# custom_line_V1_comp.net
KiCad netlist of a schematic drawn in Altium Designer
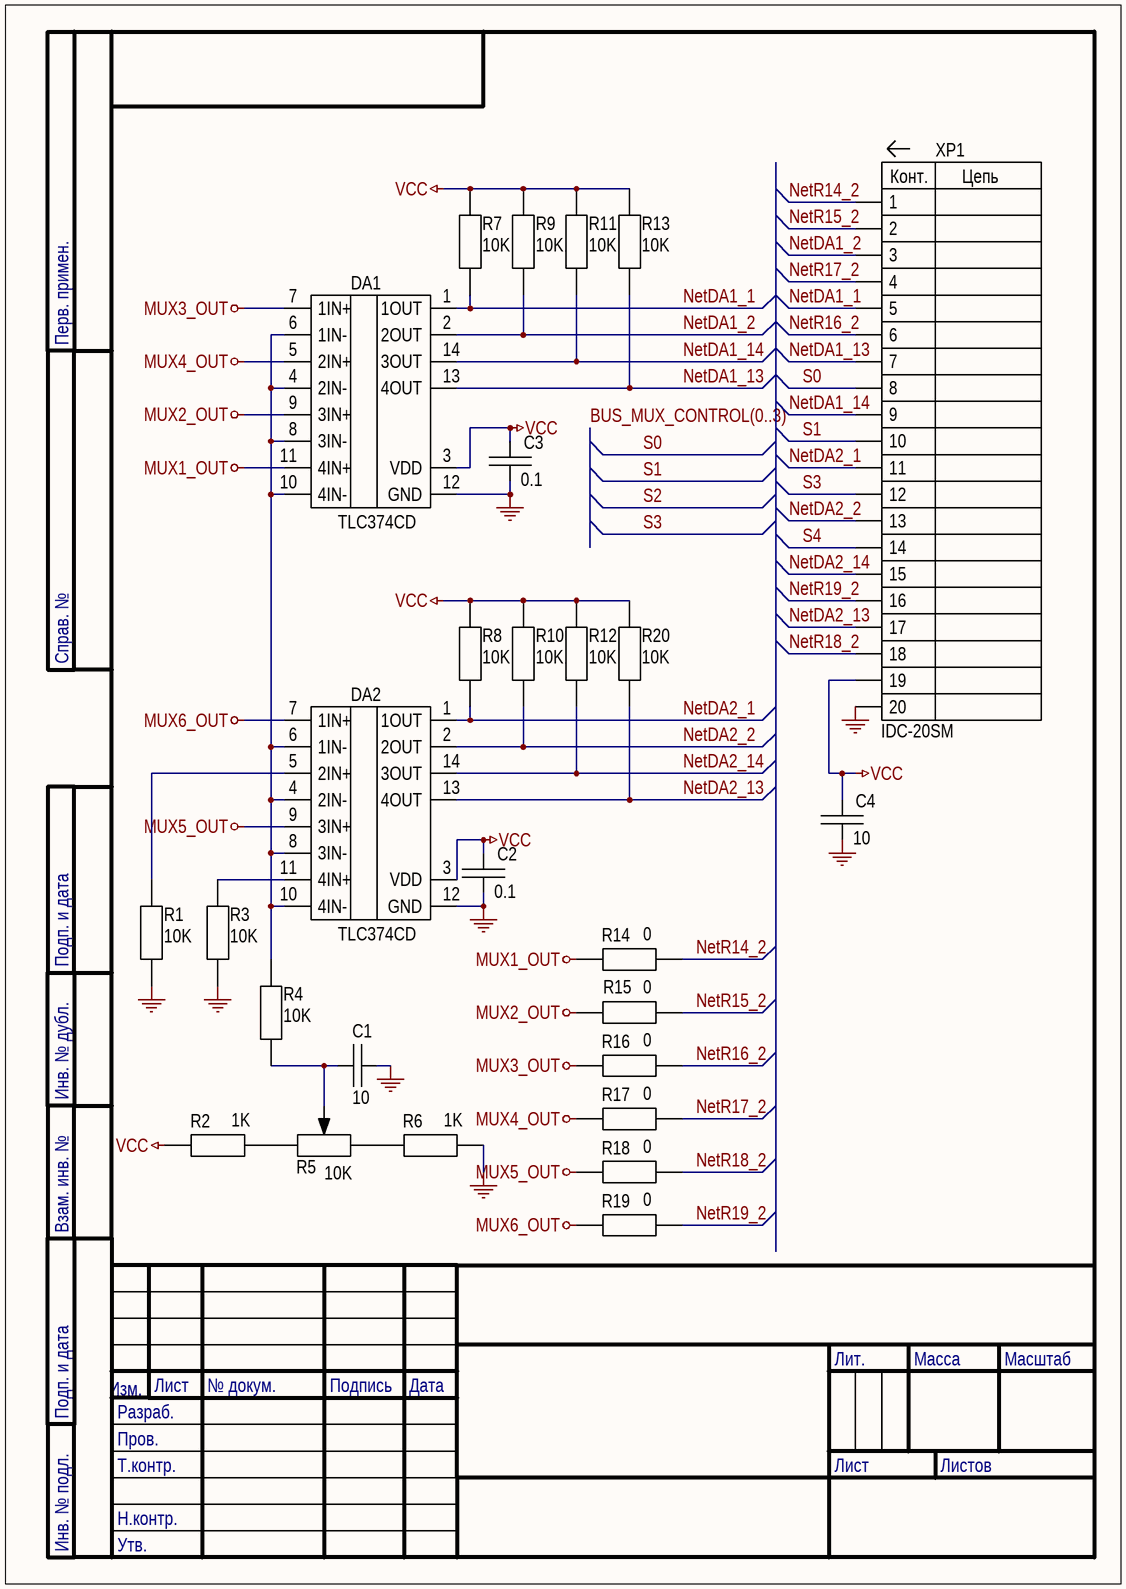
[diagram p0: custom_line_V1_comp.SchDoc]

(export (version "E")
  (design (tool "Eeschema 10.0.6"))
  (components
    (comp (ref "C1")
      (value "10")
      (footprint "CC_0805")
      (description "SMD Cap 0805,106, 16V, X5R, 10% (YAGEO)")
      (libsource (lib "my_discrete_new") (part "C"))
    )
    (comp (ref "C2")
      (value "0.1")
      (footprint "CC_0603")
      (description "SMD Cap 0603, 104, 16V, X7R, 10% (YAGEO)")
      (libsource (lib "my_discrete_new") (part "C"))
    )
    (comp (ref "C3")
      (value "0.1")
      (footprint "CC_0603")
      (description "SMD Cap 0603, 104, 16V, X7R, 10% (YAGEO)")
      (libsource (lib "my_discrete_new") (part "C"))
    )
    (comp (ref "C4")
      (value "10")
      (footprint "CC_0805")
      (description "SMD Cap 0805,106, 16V, X5R, 10% (YAGEO)")
      (libsource (lib "my_discrete_new") (part "C"))
    )
    (comp (ref "DA1")
      (value "TLC374")
      (footprint "SOIC-14")
      (description "Four Comparators (Texas Instruments)")
      (fields (field (name "TYPE") "TLC374CD"))
      (libsource (lib "my_microschems_new") (part "TLC374"))
    )
    (comp (ref "DA2")
      (value "TLC374")
      (footprint "SOIC-14")
      (description "Four Comparators (Texas Instruments)")
      (fields (field (name "TYPE") "TLC374CD"))
      (libsource (lib "my_microschems_new") (part "TLC374"))
    )
    (comp (ref "R1")
      (value "10K")
      (footprint "RC_0603_SMALL")
      (description "SMD Res 0603, 10 kOh, 1% (YAGEO)")
      (fields (field (name "POWER") "0.125W"))
      (libsource (lib "my_discrete_new") (part "R"))
    )
    (comp (ref "R2")
      (value "1K")
      (footprint "RC_0603_SMALL")
      (description "SMD Res 0603, 1 kOh, 1% (YAGEO)")
      (fields (field (name "POWER") "0.125W"))
      (libsource (lib "my_discrete_new") (part "R"))
    )
    (comp (ref "R3")
      (value "10K")
      (footprint "RC_0603_SMALL")
      (description "SMD Res 0603, 10 kOh, 1% (YAGEO)")
      (fields (field (name "POWER") "0.125W"))
      (libsource (lib "my_discrete_new") (part "R"))
    )
    (comp (ref "R4")
      (value "10K")
      (footprint "RC_0603_SMALL")
      (description "SMD Res 0603, 10 kOh, 1% (YAGEO)")
      (fields (field (name "POWER") "0.125W"))
      (libsource (lib "my_discrete_new") (part "R"))
    )
    (comp (ref "R5")
      (value "10K")
      (footprint "Res_3266W")
      (description "Trimming Potentiometer 3266W (Bourns)")
      (fields (field (name "POWER") "0.25W"))
      (libsource (lib "my_discrete_new") (part "R_potentiometer"))
    )
    (comp (ref "R6")
      (value "1K")
      (footprint "RC_0603_SMALL")
      (description "SMD Res 0603, 1 kOh, 1% (YAGEO)")
      (fields (field (name "POWER") "0.125W"))
      (libsource (lib "my_discrete_new") (part "R"))
    )
    (comp (ref "R7")
      (value "10K")
      (footprint "RC_0603_SMALL")
      (description "SMD Res 0603, 10 kOh, 1% (YAGEO)")
      (fields (field (name "POWER") "0.125W"))
      (libsource (lib "my_discrete_new") (part "R"))
    )
    (comp (ref "R8")
      (value "10K")
      (footprint "RC_0603_SMALL")
      (description "SMD Res 0603, 10 kOh, 1% (YAGEO)")
      (fields (field (name "POWER") "0.125W"))
      (libsource (lib "my_discrete_new") (part "R"))
    )
    (comp (ref "R9")
      (value "10K")
      (footprint "RC_0603_SMALL")
      (description "SMD Res 0603, 10 kOh, 1% (YAGEO)")
      (fields (field (name "POWER") "0.125W"))
      (libsource (lib "my_discrete_new") (part "R"))
    )
    (comp (ref "R10")
      (value "10K")
      (footprint "RC_0603_SMALL")
      (description "SMD Res 0603, 10 kOh, 1% (YAGEO)")
      (fields (field (name "POWER") "0.125W"))
      (libsource (lib "my_discrete_new") (part "R"))
    )
    (comp (ref "R11")
      (value "10K")
      (footprint "RC_0603_SMALL")
      (description "SMD Res 0603, 10 kOh, 1% (YAGEO)")
      (fields (field (name "POWER") "0.125W"))
      (libsource (lib "my_discrete_new") (part "R"))
    )
    (comp (ref "R12")
      (value "10K")
      (footprint "RC_0603_SMALL")
      (description "SMD Res 0603, 10 kOh, 1% (YAGEO)")
      (fields (field (name "POWER") "0.125W"))
      (libsource (lib "my_discrete_new") (part "R"))
    )
    (comp (ref "R13")
      (value "10K")
      (footprint "RC_0603_SMALL")
      (description "SMD Res 0603, 10 kOh, 1% (YAGEO)")
      (fields (field (name "POWER") "0.125W"))
      (libsource (lib "my_discrete_new") (part "R"))
    )
    (comp (ref "R14")
      (value "0")
      (footprint "RC_0603_SMALL")
      (fields (field (name "POWER") "0.125W"))
      (libsource (lib "my_discrete_new") (part "R"))
    )
    (comp (ref "R15")
      (value "0")
      (footprint "RC_0603_SMALL")
      (fields (field (name "POWER") "0.125W"))
      (libsource (lib "my_discrete_new") (part "R"))
    )
    (comp (ref "R16")
      (value "0")
      (footprint "RC_0603_SMALL")
      (fields (field (name "POWER") "0.125W"))
      (libsource (lib "my_discrete_new") (part "R"))
    )
    (comp (ref "R17")
      (value "0")
      (footprint "RC_0603_SMALL")
      (fields (field (name "POWER") "0.125W"))
      (libsource (lib "my_discrete_new") (part "R"))
    )
    (comp (ref "R18")
      (value "0")
      (footprint "RC_0603_SMALL")
      (fields (field (name "POWER") "0.125W"))
      (libsource (lib "my_discrete_new") (part "R"))
    )
    (comp (ref "R19")
      (value "0")
      (footprint "RC_0603_SMALL")
      (fields (field (name "POWER") "0.125W"))
      (libsource (lib "my_discrete_new") (part "R"))
    )
    (comp (ref "R20")
      (value "10K")
      (footprint "RC_0603_SMALL")
      (description "SMD Res 0603, 10 kOh, 1% (YAGEO)")
      (fields (field (name "POWER") "0.125W"))
      (libsource (lib "my_discrete_new") (part "R"))
    )
    (comp (ref "XP1")
      (value "IDC-20SM")
      (footprint "IDC-20SM")
      (description "Connector IDC-20SM (Connfly)")
      (libsource (lib "my_connectors_new") (part "XT_IDC-20SM"))
    )
  )
  (nets
    (net (code "2") (name "/NetDA1_1") (class "Default")
      (node (ref "DA1") (pin "1") (pinfunction "1OUT_1") (pintype "passive"))
      (node (ref "R7") (pin "2") (pinfunction "2_2") (pintype "passive"))
      (node (ref "XP1") (pin "5") (pinfunction "5_5") (pintype "passive"))
    )
    (net (code "3") (name "/NetDA1_2") (class "Default")
      (node (ref "DA1") (pin "2") (pinfunction "2OUT_2") (pintype "passive"))
      (node (ref "R9") (pin "2") (pinfunction "2_2") (pintype "passive"))
      (node (ref "XP1") (pin "3") (pinfunction "3_3") (pintype "passive"))
    )
    (net (code "4") (name "/NetDA1_13") (class "Default")
      (node (ref "DA1") (pin "13") (pinfunction "4OUT_13") (pintype "passive"))
      (node (ref "R13") (pin "2") (pinfunction "2_2") (pintype "passive"))
      (node (ref "XP1") (pin "7") (pinfunction "7_7") (pintype "passive"))
    )
    (net (code "5") (name "/NetDA1_14") (class "Default")
      (node (ref "DA1") (pin "14") (pinfunction "3OUT_14") (pintype "passive"))
      (node (ref "R11") (pin "2") (pinfunction "2_2") (pintype "passive"))
      (node (ref "XP1") (pin "9") (pinfunction "9_9") (pintype "passive"))
    )
    (net (code "6") (name "/NetDA2_1") (class "Default")
      (node (ref "DA2") (pin "1") (pinfunction "1OUT_1") (pintype "passive"))
      (node (ref "R8") (pin "2") (pinfunction "2_2") (pintype "passive"))
      (node (ref "XP1") (pin "11") (pinfunction "11_11") (pintype "passive"))
    )
    (net (code "7") (name "/NetDA2_2") (class "Default")
      (node (ref "DA2") (pin "2") (pinfunction "2OUT_2") (pintype "passive"))
      (node (ref "R10") (pin "2") (pinfunction "2_2") (pintype "passive"))
      (node (ref "XP1") (pin "13") (pinfunction "13_13") (pintype "passive"))
    )
    (net (code "8") (name "/NetDA2_13") (class "Default")
      (node (ref "DA2") (pin "13") (pinfunction "4OUT_13") (pintype "passive"))
      (node (ref "R20") (pin "2") (pinfunction "2_2") (pintype "passive"))
      (node (ref "XP1") (pin "17") (pinfunction "17_17") (pintype "passive"))
    )
    (net (code "9") (name "/NetDA2_14") (class "Default")
      (node (ref "DA2") (pin "14") (pinfunction "3OUT_14") (pintype "passive"))
      (node (ref "R12") (pin "2") (pinfunction "2_2") (pintype "passive"))
      (node (ref "XP1") (pin "15") (pinfunction "15_15") (pintype "passive"))
    )
    (net (code "10") (name "/NetR14_2") (class "Default")
      (node (ref "R14") (pin "2") (pinfunction "2_2") (pintype "passive"))
      (node (ref "XP1") (pin "1") (pinfunction "1_1") (pintype "passive"))
    )
    (net (code "11") (name "/NetR15_2") (class "Default")
      (node (ref "R15") (pin "2") (pinfunction "2_2") (pintype "passive"))
      (node (ref "XP1") (pin "2") (pinfunction "2_2") (pintype "passive"))
    )
    (net (code "12") (name "/NetR16_2") (class "Default")
      (node (ref "R16") (pin "2") (pinfunction "2_2") (pintype "passive"))
      (node (ref "XP1") (pin "6") (pinfunction "6_6") (pintype "passive"))
    )
    (net (code "13") (name "/NetR17_2") (class "Default")
      (node (ref "R17") (pin "2") (pinfunction "2_2") (pintype "passive"))
      (node (ref "XP1") (pin "4") (pinfunction "4_4") (pintype "passive"))
    )
    (net (code "14") (name "/NetR18_2") (class "Default")
      (node (ref "R18") (pin "2") (pinfunction "2_2") (pintype "passive"))
      (node (ref "XP1") (pin "18") (pinfunction "18_18") (pintype "passive"))
    )
    (net (code "15") (name "/NetR19_2") (class "Default")
      (node (ref "R19") (pin "2") (pinfunction "2_2") (pintype "passive"))
      (node (ref "XP1") (pin "16") (pinfunction "16_16") (pintype "passive"))
    )
    (net (code "16") (name "/S0") (class "Default")
      (node (ref "XP1") (pin "8") (pinfunction "8_8") (pintype "passive"))
    )
    (net (code "17") (name "/S1") (class "Default")
      (node (ref "XP1") (pin "10") (pinfunction "10_10") (pintype "passive"))
    )
    (net (code "19") (name "/S3") (class "Default")
      (node (ref "XP1") (pin "12") (pinfunction "12_12") (pintype "passive"))
    )
    (net (code "20") (name "/S4") (class "Default")
      (node (ref "XP1") (pin "14") (pinfunction "14_14") (pintype "passive"))
    )
    (net (code "22") (name "GND") (class "Default")
      (node (ref "C1") (pin "1") (pinfunction "1_1") (pintype "passive"))
      (node (ref "C2") (pin "1") (pinfunction "1_1") (pintype "passive"))
      (node (ref "C3") (pin "1") (pinfunction "1_1") (pintype "passive"))
      (node (ref "C4") (pin "1") (pinfunction "1_1") (pintype "passive"))
      (node (ref "DA1") (pin "12") (pinfunction "GND_12") (pintype "power_in"))
      (node (ref "DA2") (pin "12") (pinfunction "GND_12") (pintype "power_in"))
      (node (ref "R1") (pin "2") (pinfunction "2_2") (pintype "passive"))
      (node (ref "R3") (pin "2") (pinfunction "2_2") (pintype "passive"))
      (node (ref "R6") (pin "2") (pinfunction "2_2") (pintype "passive"))
      (node (ref "XP1") (pin "20") (pinfunction "20_20") (pintype "passive"))
    )
    (net (code "23") (name "MUX1_OUT") (class "Default")
      (node (ref "DA1") (pin "11") (pinfunction "4IN+_11") (pintype "passive"))
      (node (ref "R14") (pin "1") (pinfunction "1_1") (pintype "passive"))
    )
    (net (code "24") (name "MUX2_OUT") (class "Default")
      (node (ref "DA1") (pin "9") (pinfunction "3IN+_9") (pintype "passive"))
      (node (ref "R15") (pin "1") (pinfunction "1_1") (pintype "passive"))
    )
    (net (code "25") (name "MUX3_OUT") (class "Default")
      (node (ref "DA1") (pin "7") (pinfunction "1IN+_7") (pintype "passive"))
      (node (ref "R16") (pin "1") (pinfunction "1_1") (pintype "passive"))
    )
    (net (code "26") (name "MUX4_OUT") (class "Default")
      (node (ref "DA1") (pin "5") (pinfunction "2IN+_5") (pintype "passive"))
      (node (ref "R17") (pin "1") (pinfunction "1_1") (pintype "passive"))
    )
    (net (code "27") (name "MUX5_OUT") (class "Default")
      (node (ref "DA2") (pin "9") (pinfunction "3IN+_9") (pintype "passive"))
      (node (ref "R18") (pin "1") (pinfunction "1_1") (pintype "passive"))
    )
    (net (code "28") (name "MUX6_OUT") (class "Default")
      (node (ref "DA2") (pin "7") (pinfunction "1IN+_7") (pintype "passive"))
      (node (ref "R19") (pin "1") (pinfunction "1_1") (pintype "passive"))
    )
    (net (code "29") (name "Net-(C1-Pad2)") (class "Default")
      (node (ref "C1") (pin "2") (pinfunction "2_2") (pintype "passive"))
      (node (ref "R4") (pin "2") (pinfunction "2_2") (pintype "passive"))
      (node (ref "R5") (pin "2") (pinfunction "2_2") (pintype "passive"))
    )
    (net (code "30") (name "Net-(DA1-1IN-)") (class "Default")
      (node (ref "DA1") (pin "10") (pinfunction "4IN-_10") (pintype "passive"))
      (node (ref "DA1") (pin "4") (pinfunction "2IN-_4") (pintype "passive"))
      (node (ref "DA1") (pin "6") (pinfunction "1IN-_6") (pintype "passive"))
      (node (ref "DA1") (pin "8") (pinfunction "3IN-_8") (pintype "passive"))
      (node (ref "DA2") (pin "10") (pinfunction "4IN-_10") (pintype "passive"))
      (node (ref "DA2") (pin "4") (pinfunction "2IN-_4") (pintype "passive"))
      (node (ref "DA2") (pin "6") (pinfunction "1IN-_6") (pintype "passive"))
      (node (ref "DA2") (pin "8") (pinfunction "3IN-_8") (pintype "passive"))
      (node (ref "R4") (pin "1") (pinfunction "1_1") (pintype "passive"))
    )
    (net (code "31") (name "Net-(DA2-2IN+)") (class "Default")
      (node (ref "DA2") (pin "5") (pinfunction "2IN+_5") (pintype "passive"))
      (node (ref "R1") (pin "1") (pinfunction "1_1") (pintype "passive"))
    )
    (net (code "32") (name "Net-(DA2-4IN+)") (class "Default")
      (node (ref "DA2") (pin "11") (pinfunction "4IN+_11") (pintype "passive"))
      (node (ref "R3") (pin "1") (pinfunction "1_1") (pintype "passive"))
    )
    (net (code "33") (name "Net-(R2-Pad2)") (class "Default")
      (node (ref "R2") (pin "2") (pinfunction "2_2") (pintype "passive"))
      (node (ref "R5") (pin "1") (pinfunction "1_1") (pintype "passive"))
    )
    (net (code "34") (name "Net-(R5-Pad3)") (class "Default")
      (node (ref "R5") (pin "3") (pinfunction "3_3") (pintype "passive"))
      (node (ref "R6") (pin "1") (pinfunction "1_1") (pintype "passive"))
    )
    (net (code "35") (name "VCC") (class "Default")
      (node (ref "C2") (pin "2") (pinfunction "2_2") (pintype "passive"))
      (node (ref "C3") (pin "2") (pinfunction "2_2") (pintype "passive"))
      (node (ref "C4") (pin "2") (pinfunction "2_2") (pintype "passive"))
      (node (ref "DA1") (pin "3") (pinfunction "VDD_3") (pintype "power_in"))
      (node (ref "DA2") (pin "3") (pinfunction "VDD_3") (pintype "power_in"))
      (node (ref "R10") (pin "1") (pinfunction "1_1") (pintype "passive"))
      (node (ref "R11") (pin "1") (pinfunction "1_1") (pintype "passive"))
      (node (ref "R12") (pin "1") (pinfunction "1_1") (pintype "passive"))
      (node (ref "R13") (pin "1") (pinfunction "1_1") (pintype "passive"))
      (node (ref "R2") (pin "1") (pinfunction "1_1") (pintype "passive"))
      (node (ref "R20") (pin "1") (pinfunction "1_1") (pintype "passive"))
      (node (ref "R7") (pin "1") (pinfunction "1_1") (pintype "passive"))
      (node (ref "R8") (pin "1") (pinfunction "1_1") (pintype "passive"))
      (node (ref "R9") (pin "1") (pinfunction "1_1") (pintype "passive"))
      (node (ref "XP1") (pin "19") (pinfunction "19_19") (pintype "passive"))
    )
  )
)
